# 3V3REG.net
KiCad netlist of a schematic drawn in Altium Designer
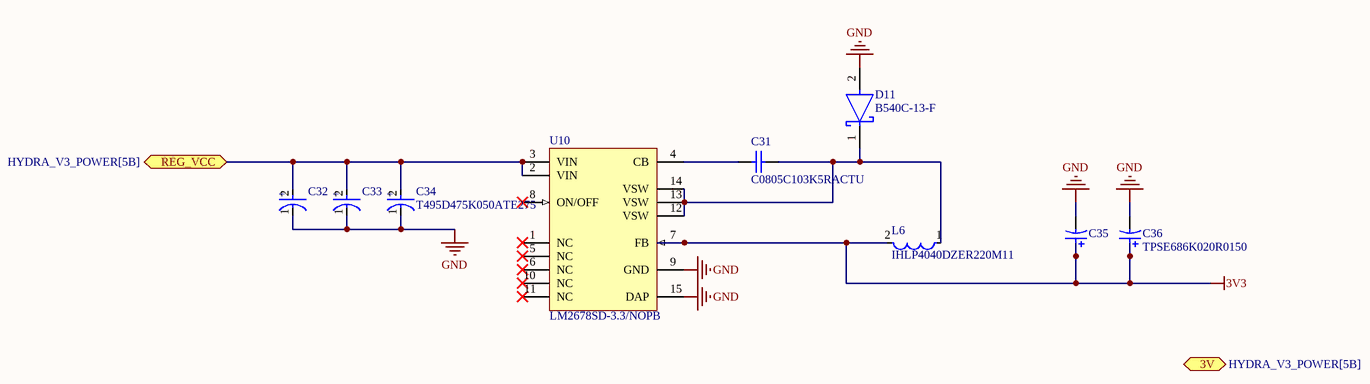
[diagram p0: 3V3REG.SchDoc]

(export (version "E")
  (design (tool "Eeschema 10.0.6"))
  (components
    (comp (ref "C31")
      (value "C0805C103K5RACTU")
      (footprint "CAPC2013X88X50LL20T25")
      (fields (field (name "MANUFACTURER") "Kemet"))
      (libsource (lib "Altium Content Vault") (part "CAP"))
    )
    (comp (ref "C32")
      (value "~")
      (footprint "FP-T495D475K050ATE275-MFG")
      (description "CAP TANT 4.7UF 10% 50V 2917")
      (fields (field (name "TOLERANCE") "10%"))
      (libsource (lib "Altium Content Vault") (part "a00bbbee19879c290e62620ae7e47b1"))
    )
    (comp (ref "C33")
      (value "~")
      (footprint "FP-T495D475K050ATE275-MFG")
      (description "CAP TANT 4.7UF 10% 50V 2917")
      (fields (field (name "TOLERANCE") "10%"))
      (libsource (lib "Altium Content Vault") (part "a00bbbee19879c290e62620ae7e47b1"))
    )
    (comp (ref "C34")
      (value "T495D475K050ATE275")
      (footprint "FP-T495D475K050ATE275-MFG")
      (description "CAP TANT 4.7UF 10% 50V 2917")
      (fields (field (name "TOLERANCE") "10%"))
      (libsource (lib "Altium Content Vault") (part "a00bbbee19879c290e62620ae7e47b1"))
    )
    (comp (ref "C35")
      (value "~")
      (footprint "CAPMP7344X43-T_V")
      (description "Low ESR, 68 uF, 20 V, +/- 10%, -55 to 125 degC, 2-Pin SMD, RoHS, Tape and Reel")
      (fields (field (name "MANUFACTURER") "AVX") (field (name "VOLTAGE") "20VDC"))
      (libsource (lib "Altium Content Vault") (part "CAP-P-2"))
    )
    (comp (ref "C36")
      (value "TPSE686K020R0150")
      (footprint "CAPMP7344X43-T_V")
      (description "Low ESR, 68 uF, 20 V, +/- 10%, -55 to 125 degC, 2-Pin SMD, RoHS, Tape and Reel")
      (fields (field (name "MANUFACTURER") "AVX") (field (name "VOLTAGE") "20VDC"))
      (libsource (lib "Altium Content Vault") (part "CAP-P-2"))
    )
    (comp (ref "D11")
      (value "B540C-13-F")
      (footprint "FP-SMC-MFG")
      (description "DIODE SCHOTTKY 40V 5A SMC")
      (fields
        (field (name "OCTOPART") "https://octopart.com/b540c-13-f-diodes+inc.-325873")
        (field (name "MANUFACTURER") "Diodes Inc.")
      )
      (libsource (lib "Altium Content Vault") (part "1d6ec82d83fb6aee721767c19dac4b9"))
    )
    (comp (ref "L6")
      (value "IHLP4040DZER220M11")
      (footprint "FP-IHLP-4040DZ-FP_3_124x3-MFG")
      (description "Commercial Inductors, Low DCR Series 22uH 5A 66mΩ 20%")
      (fields (field (name "TOLERANCE") "20%"))
      (libsource (lib "Altium Content Vault") (part "725321dda6339637d4d059423bc1c3c"))
    )
    (comp (ref "U10")
      (value "LM2678SD-3.3/NOPB")
      (footprint "NHM0014A_V")
      (description "SIMPLE SWITCHER® High Efficiency 5A Step-Down Voltage Regulator, 14-pin LLP, Pb-Free")
      (fields (field (name "MANUFACTURER") "Texas Instruments"))
      (libsource (lib "Altium Content Vault") (part "PM-REG-LM2678SD"))
    )
  )
  (nets
    (net (code "2") (name "/REG_VCC") (class "Default")
      (node (ref "C32") (pin "2") (pinfunction "A_2") (pintype "passive"))
      (node (ref "C33") (pin "2") (pinfunction "A_2") (pintype "passive"))
      (node (ref "C34") (pin "2") (pinfunction "A_2") (pintype "passive"))
      (node (ref "U10") (pin "2") (pinfunction "VIN_2") (pintype "power_in"))
      (node (ref "U10") (pin "3") (pinfunction "VIN_3") (pintype "power_in"))
    )
    (net (code "3") (name "3V3") (class "Default")
      (node (ref "C35") (pin "1") (pinfunction "1_1") (pintype "passive"))
      (node (ref "C36") (pin "1") (pinfunction "1_1") (pintype "passive"))
      (node (ref "L6") (pin "2") (pinfunction "2_2") (pintype "passive"))
      (node (ref "U10") (pin "7") (pinfunction "FB_7") (pintype "input"))
    )
    (net (code "4") (name "GND") (class "Default")
      (node (ref "C32") (pin "1") (pinfunction "C_1") (pintype "passive"))
      (node (ref "C33") (pin "1") (pinfunction "C_1") (pintype "passive"))
      (node (ref "C34") (pin "1") (pinfunction "C_1") (pintype "passive"))
      (node (ref "C35") (pin "2") (pinfunction "2_2") (pintype "passive"))
      (node (ref "C36") (pin "2") (pinfunction "2_2") (pintype "passive"))
      (node (ref "D11") (pin "2") (pinfunction "A_2") (pintype "passive"))
      (node (ref "U10") (pin "15") (pinfunction "DAP_15") (pintype "power_in"))
      (node (ref "U10") (pin "9") (pinfunction "GND_9") (pintype "power_in"))
    )
    (net (code "5") (name "Net-(D11-C)") (class "Default")
      (node (ref "C31") (pin "2") (pinfunction "2_2") (pintype "passive"))
      (node (ref "D11") (pin "1") (pinfunction "C_1") (pintype "passive"))
      (node (ref "L6") (pin "1") (pinfunction "1_1") (pintype "passive"))
      (node (ref "U10") (pin "12") (pinfunction "VSW_12") (pintype "power_in"))
      (node (ref "U10") (pin "13") (pinfunction "VSW_13") (pintype "power_in"))
      (node (ref "U10") (pin "14") (pinfunction "VSW_14") (pintype "power_in"))
    )
    (net (code "6") (name "Net-(U10-CB)") (class "Default")
      (node (ref "C31") (pin "1") (pinfunction "1_1") (pintype "passive"))
      (node (ref "U10") (pin "4") (pinfunction "CB_4") (pintype "passive"))
    )
    (net (code "7") (name "unconnected-(U10-NC-Pad1)") (class "Default")
      (node (ref "U10") (pin "1") (pinfunction "NC_1") (pintype "passive+no_connect"))
    )
    (net (code "8") (name "unconnected-(U10-NC-Pad5)") (class "Default")
      (node (ref "U10") (pin "5") (pinfunction "NC_5") (pintype "passive+no_connect"))
    )
    (net (code "9") (name "unconnected-(U10-NC-Pad6)") (class "Default")
      (node (ref "U10") (pin "6") (pinfunction "NC_6") (pintype "passive+no_connect"))
    )
    (net (code "10") (name "unconnected-(U10-NC-Pad10)") (class "Default")
      (node (ref "U10") (pin "10") (pinfunction "NC_10") (pintype "passive+no_connect"))
    )
    (net (code "11") (name "unconnected-(U10-NC-Pad11)") (class "Default")
      (node (ref "U10") (pin "11") (pinfunction "NC_11") (pintype "passive+no_connect"))
    )
    (net (code "12") (name "unconnected-(U10-ON{slash}OFF-Pad8)") (class "Default")
      (node (ref "U10") (pin "8") (pinfunction "ON/OFF_8") (pintype "input+no_connect"))
    )
  )
)
